# array.net
KiCad netlist of a schematic drawn in Altium Designer
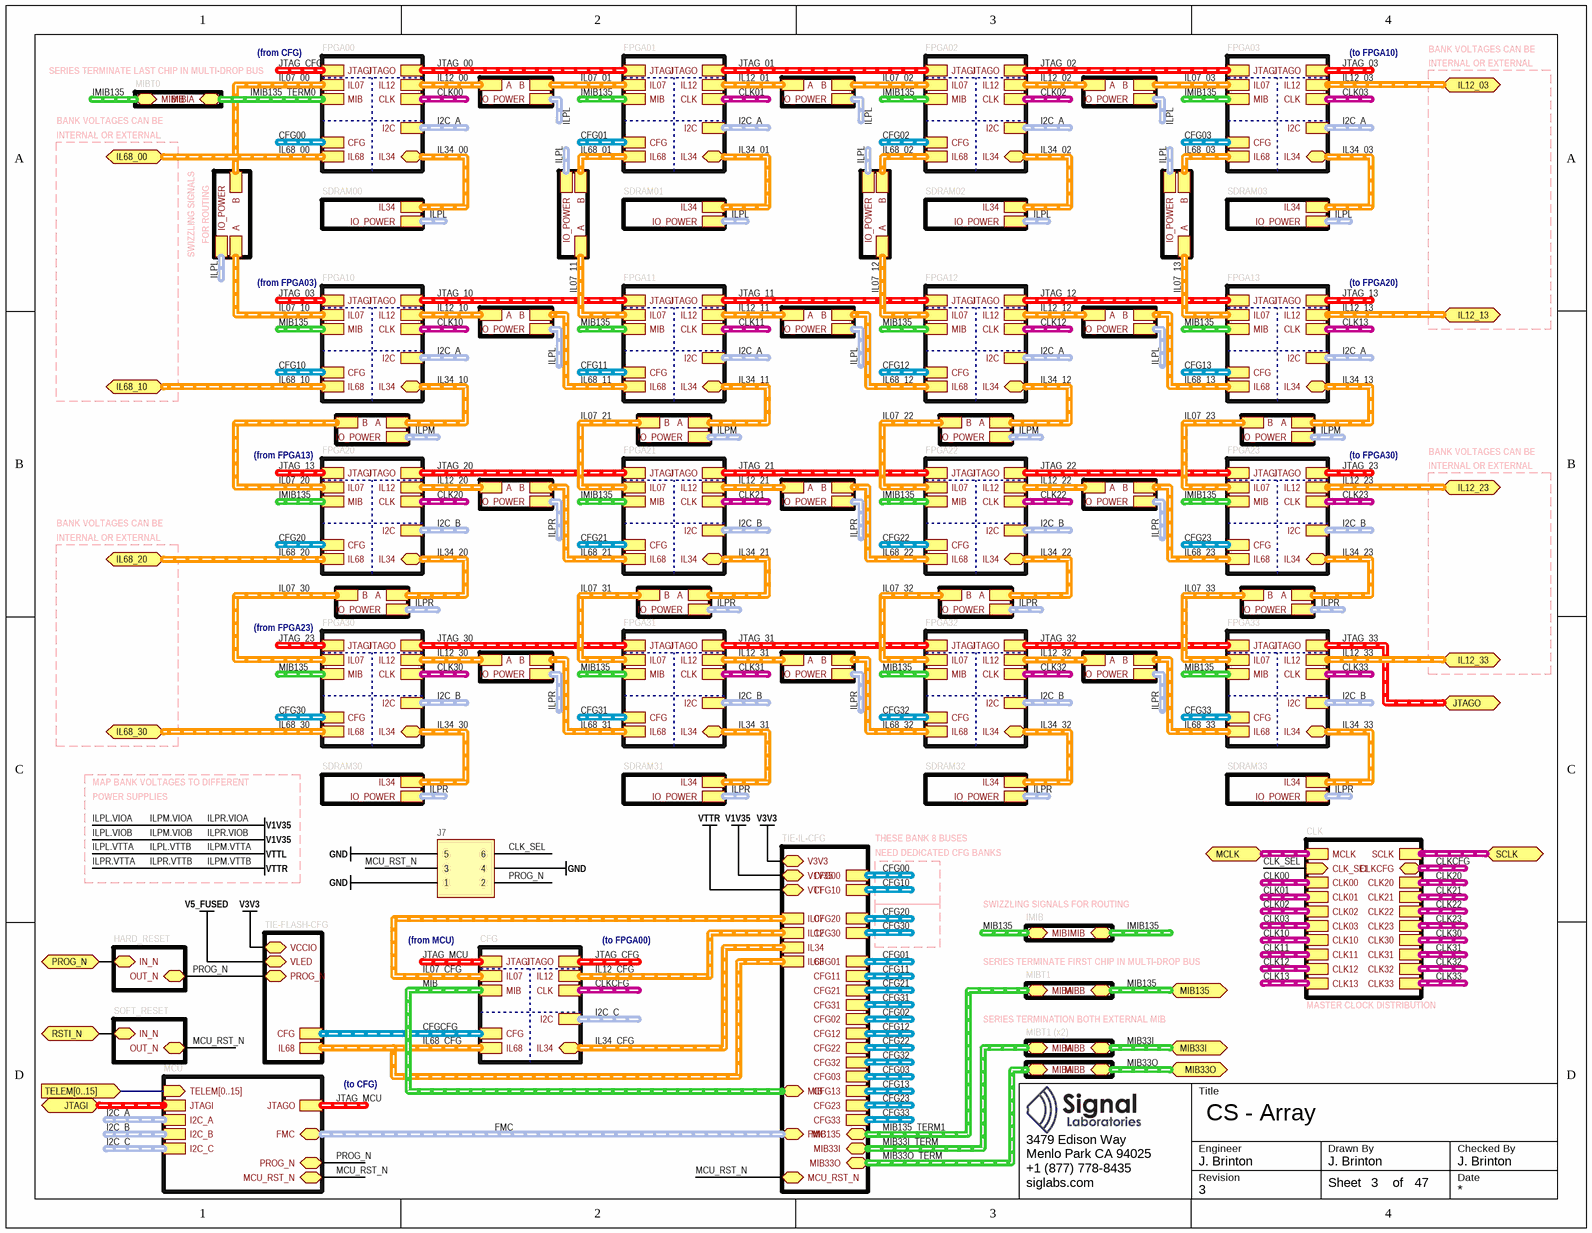
[diagram p0: array.SchDoc]

(export (version "E")
  (design (tool "Eeschema 10.0.6"))
  (components
    (comp (ref "J7")
      (value "GRPB032MWCN-RC")
      (footprint "sullins:GRPB032MWCN")
      (description "Male Header, 0.050\" Pitch, Right Angle, 2x3 Position")
      (fields (field (name "MANUFACTURER") "Sullins"))
      (libsource (lib "sullins") (part "GRPB032MWCN-RC"))
    )
  )
  (nets
    (net (code "156") (name "/CLK_SEL") (class "Default")
      (node (ref "J7") (pin "6") (pinfunction "6_6") (pintype "passive"))
    )
    (net (code "159") (name "/MCU_RST_N") (class "Default")
      (node (ref "J7") (pin "3") (pinfunction "3_3") (pintype "passive"))
    )
    (net (code "160") (name "/PROG_N") (class "Default")
      (node (ref "J7") (pin "2") (pinfunction "2_2") (pintype "passive"))
    )
    (net (code "300") (name "GND") (class "Default")
      (node (ref "J7") (pin "1") (pinfunction "1_1") (pintype "passive"))
      (node (ref "J7") (pin "4") (pinfunction "4_4") (pintype "passive"))
      (node (ref "J7") (pin "5") (pinfunction "5_5") (pintype "passive"))
    )
  )
)
